# esp8266-lights-v3.net
KiCad netlist of a schematic drawn in EAGLE
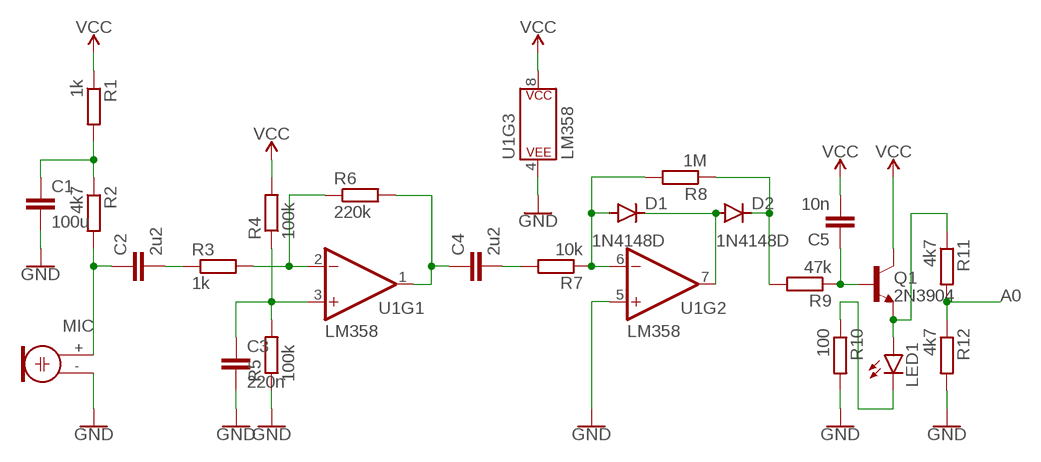
[diagram p0: schematic, sheet 1]
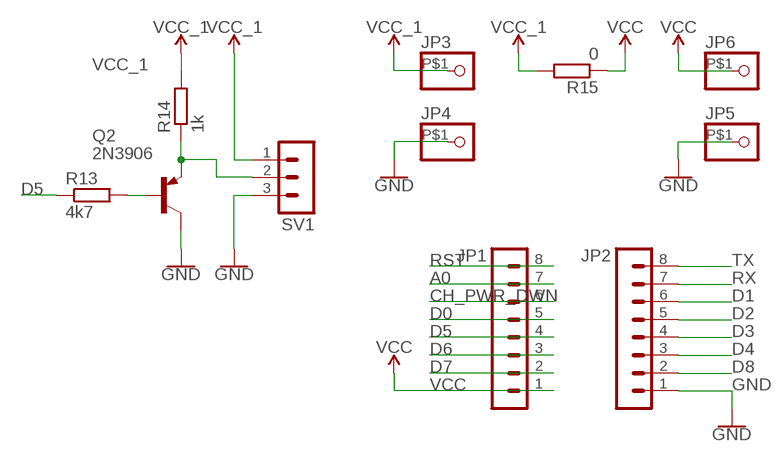
[diagram p1: schematic, sheet 2]

(export (version "E")
  (design (tool "Eeschema 10.0.6"))
  (components
    (comp (ref "JP1")
      (value "MA08-1")
      (footprint "eagle-import:MA08-1")
      (libsource (lib "eagle-import") (part "MA08-1"))
    )
    (comp (ref "JP2")
      (value "MA08-1")
      (footprint "eagle-import:MA08-1")
      (libsource (lib "eagle-import") (part "MA08-1"))
    )
    (comp (ref "JP3")
      (value "PINHD-1X1-BIGPOGO")
      (footprint "eagle-import:1X1-BIGPOGO")
      (libsource (lib "eagle-import") (part "PINHD-1X1-BIGPOGO"))
    )
    (comp (ref "JP4")
      (value "PINHD-1X1-BIGPOGO")
      (footprint "eagle-import:1X1-BIGPOGO")
      (libsource (lib "eagle-import") (part "PINHD-1X1-BIGPOGO"))
    )
    (comp (ref "JP5")
      (value "PINHD-1X1-BIGPOGO")
      (footprint "eagle-import:1X1-BIGPOGO")
      (libsource (lib "eagle-import") (part "PINHD-1X1-BIGPOGO"))
    )
    (comp (ref "JP6")
      (value "PINHD-1X1-BIGPOGO")
      (footprint "eagle-import:1X1-BIGPOGO")
      (libsource (lib "eagle-import") (part "PINHD-1X1-BIGPOGO"))
    )
    (comp (ref "Q2")
      (value "2N3906")
      (footprint "eagle-import:TO92")
      (libsource (lib "eagle-import") (part "2N3906"))
    )
    (comp (ref "R13")
      (value "4k7")
      (footprint "eagle-import:0309_10")
      (libsource (lib "eagle-import") (part "R-EU_0309/10"))
    )
    (comp (ref "R14")
      (value "1k")
      (footprint "eagle-import:0309_10")
      (libsource (lib "eagle-import") (part "R-EU_0309/10"))
    )
    (comp (ref "R15")
      (value "0")
      (footprint "eagle-import:0309_10")
      (libsource (lib "eagle-import") (part "R-EU_0309/10"))
    )
    (comp (ref "SV1")
      (value "MA03-1")
      (footprint "eagle-import:MA03-1")
      (libsource (lib "eagle-import") (part "MA03-1"))
    )
    (comp (ref "C1")
      (value "100u")
      (footprint "eagle-import:C050-024X044")
      (libsource (lib "eagle-import") (part "C-EU050-024X044"))
    )
    (comp (ref "C2")
      (value "2u2")
      (footprint "eagle-import:C050-024X044")
      (libsource (lib "eagle-import") (part "C-EU050-024X044"))
    )
    (comp (ref "C3")
      (value "220n")
      (footprint "eagle-import:C050-024X044")
      (libsource (lib "eagle-import") (part "C-EU050-024X044"))
    )
    (comp (ref "C4")
      (value "2u2")
      (footprint "eagle-import:C050-024X044")
      (libsource (lib "eagle-import") (part "C-EU050-024X044"))
    )
    (comp (ref "C5")
      (value "10n")
      (footprint "eagle-import:C050-024X044")
      (libsource (lib "eagle-import") (part "C-EU050-024X044"))
    )
    (comp (ref "D1")
      (value "1N4148D")
      (footprint "eagle-import:DO35-10")
      (libsource (lib "eagle-import") (part "1N4148DO35-10"))
    )
    (comp (ref "D2")
      (value "1N4148D")
      (footprint "eagle-import:DO35-10")
      (libsource (lib "eagle-import") (part "1N4148DO35-10"))
    )
    (comp (ref "LED1")
      (value "LED5MM")
      (footprint "eagle-import:LED5MM")
      (libsource (lib "eagle-import") (part "LED5MM"))
    )
    (comp (ref "MIC")
      (value "ELECTRET")
      (footprint "eagle-import:9.7ELECTRET")
      (libsource (lib "eagle-import") (part "ELECTRET"))
    )
    (comp (ref "Q1")
      (value "2N3904")
      (footprint "eagle-import:TO92")
      (libsource (lib "eagle-import") (part "2N3904"))
    )
    (comp (ref "R1")
      (value "1k")
      (footprint "eagle-import:0309_10")
      (libsource (lib "eagle-import") (part "R-EU_0309/10"))
    )
    (comp (ref "R2")
      (value "4k7")
      (footprint "eagle-import:0309_10")
      (libsource (lib "eagle-import") (part "R-EU_0309/10"))
    )
    (comp (ref "R3")
      (value "1k")
      (footprint "eagle-import:0309_10")
      (libsource (lib "eagle-import") (part "R-EU_0309/10"))
    )
    (comp (ref "R4")
      (value "100k")
      (footprint "eagle-import:0309_10")
      (libsource (lib "eagle-import") (part "R-EU_0309/10"))
    )
    (comp (ref "R5")
      (value "100k")
      (footprint "eagle-import:0309_10")
      (libsource (lib "eagle-import") (part "R-EU_0309/10"))
    )
    (comp (ref "R6")
      (value "220k")
      (footprint "eagle-import:0309_10")
      (libsource (lib "eagle-import") (part "R-EU_0309/10"))
    )
    (comp (ref "R7")
      (value "10k")
      (footprint "eagle-import:0309_10")
      (libsource (lib "eagle-import") (part "R-EU_0309/10"))
    )
    (comp (ref "R8")
      (value "1M")
      (footprint "eagle-import:0309_10")
      (libsource (lib "eagle-import") (part "R-EU_0309/10"))
    )
    (comp (ref "R9")
      (value "47k")
      (footprint "eagle-import:0309_10")
      (libsource (lib "eagle-import") (part "R-EU_0309/10"))
    )
    (comp (ref "R10")
      (value "100")
      (footprint "eagle-import:0309_10")
      (libsource (lib "eagle-import") (part "R-EU_0309/10"))
    )
    (comp (ref "R11")
      (value "4k7")
      (footprint "eagle-import:0309_10")
      (libsource (lib "eagle-import") (part "R-EU_0309/10"))
    )
    (comp (ref "R12")
      (value "4k7")
      (footprint "eagle-import:0309_10")
      (libsource (lib "eagle-import") (part "R-EU_0309/10"))
    )
    (comp (ref "U1")
      (value "LM358")
      (footprint "eagle-import:DIP08-KIT")
      (libsource (lib "eagle-import") (part "LM358KIT"))
    )
  )
  (nets
    (net (code "1") (name "A0") (class "Default")
      (node (ref "JP1") (pin "7") (pinfunction "7_7") (pintype "passive"))
      (node (ref "R11") (pin "2") (pinfunction "2_2") (pintype "passive"))
      (node (ref "R12") (pin "1") (pinfunction "1_1") (pintype "passive"))
    )
    (net (code "2") (name "CH_PWR_DWN") (class "Default")
      (node (ref "JP1") (pin "6") (pinfunction "6_6") (pintype "passive"))
    )
    (net (code "3") (name "D0") (class "Default")
      (node (ref "JP1") (pin "5") (pinfunction "5_5") (pintype "passive"))
    )
    (net (code "4") (name "D1") (class "Default")
      (node (ref "JP2") (pin "6") (pinfunction "6_6") (pintype "passive"))
    )
    (net (code "5") (name "D2") (class "Default")
      (node (ref "JP2") (pin "5") (pinfunction "5_5") (pintype "passive"))
    )
    (net (code "6") (name "D3") (class "Default")
      (node (ref "JP2") (pin "4") (pinfunction "4_4") (pintype "passive"))
    )
    (net (code "7") (name "D4") (class "Default")
      (node (ref "JP2") (pin "3") (pinfunction "3_3") (pintype "passive"))
    )
    (net (code "8") (name "D5") (class "Default")
      (node (ref "JP1") (pin "4") (pinfunction "4_4") (pintype "passive"))
      (node (ref "R13") (pin "1") (pinfunction "1_1") (pintype "passive"))
    )
    (net (code "9") (name "D6") (class "Default")
      (node (ref "JP1") (pin "3") (pinfunction "3_3") (pintype "passive"))
    )
    (net (code "10") (name "D7") (class "Default")
      (node (ref "JP1") (pin "2") (pinfunction "2_2") (pintype "passive"))
    )
    (net (code "11") (name "D8") (class "Default")
      (node (ref "JP2") (pin "2") (pinfunction "2_2") (pintype "passive"))
    )
    (net (code "12") (name "GND") (class "Default")
      (node (ref "C1") (pin "2") (pinfunction "2_2") (pintype "passive"))
      (node (ref "C3") (pin "2") (pinfunction "2_2") (pintype "passive"))
      (node (ref "JP2") (pin "1") (pinfunction "1_1") (pintype "passive"))
      (node (ref "JP4") (pin "P$1") (pinfunction "1_P$1") (pintype "passive"))
      (node (ref "JP5") (pin "P$1") (pinfunction "1_P$1") (pintype "passive"))
      (node (ref "MIC") (pin "-") (pinfunction "1_-") (pintype "passive"))
      (node (ref "Q2") (pin "1") (pinfunction "C_1") (pintype "passive"))
      (node (ref "R10") (pin "2") (pinfunction "2_2") (pintype "passive"))
      (node (ref "R12") (pin "2") (pinfunction "2_2") (pintype "passive"))
      (node (ref "R5") (pin "1") (pinfunction "1_1") (pintype "passive"))
      (node (ref "SV1") (pin "3") (pinfunction "3_3") (pintype "passive"))
      (node (ref "U1") (pin "4") (pinfunction "P$V-_4") (pintype "bidirectional"))
      (node (ref "U1") (pin "5") (pinfunction "+IN_5") (pintype "input"))
    )
    (net (code "13") (name "Net-(C1-Pad1)") (class "Default")
      (node (ref "C1") (pin "1") (pinfunction "1_1") (pintype "passive"))
      (node (ref "R1") (pin "2") (pinfunction "2_2") (pintype "passive"))
      (node (ref "R2") (pin "1") (pinfunction "1_1") (pintype "passive"))
    )
    (net (code "14") (name "Net-(C2-Pad2)") (class "Default")
      (node (ref "C2") (pin "2") (pinfunction "2_2") (pintype "passive"))
      (node (ref "R3") (pin "1") (pinfunction "1_1") (pintype "passive"))
    )
    (net (code "15") (name "Net-(C4-Pad2)") (class "Default")
      (node (ref "C4") (pin "2") (pinfunction "2_2") (pintype "passive"))
      (node (ref "R7") (pin "2") (pinfunction "2_2") (pintype "passive"))
    )
    (net (code "16") (name "Net-(D2-PadC)") (class "Default")
      (node (ref "D2") (pin "C") (pinfunction "C_C") (pintype "passive"))
      (node (ref "R8") (pin "1") (pinfunction "1_1") (pintype "passive"))
      (node (ref "R9") (pin "2") (pinfunction "2_2") (pintype "passive"))
    )
    (net (code "17") (name "Net-(LED1-C)") (class "Default")
      (node (ref "LED1") (pin "K") (pinfunction "C_K") (pintype "passive"))
      (node (ref "R10") (pin "1") (pinfunction "1_1") (pintype "passive"))
    )
    (net (code "18") (name "Net-(MIC-2)") (class "Default")
      (node (ref "C2") (pin "1") (pinfunction "1_1") (pintype "passive"))
      (node (ref "MIC") (pin "+") (pinfunction "2_+") (pintype "passive"))
      (node (ref "R2") (pin "2") (pinfunction "2_2") (pintype "passive"))
    )
    (net (code "19") (name "Net-(Q1-B)") (class "Default")
      (node (ref "C5") (pin "1") (pinfunction "1_1") (pintype "passive"))
      (node (ref "Q1") (pin "2") (pinfunction "B_2") (pintype "passive"))
      (node (ref "R9") (pin "1") (pinfunction "1_1") (pintype "passive"))
    )
    (net (code "20") (name "Net-(Q1-E)") (class "Default")
      (node (ref "LED1") (pin "A") (pinfunction "A_A") (pintype "passive"))
      (node (ref "Q1") (pin "3") (pinfunction "E_3") (pintype "passive"))
      (node (ref "R11") (pin "1") (pinfunction "1_1") (pintype "passive"))
    )
    (net (code "21") (name "Net-(Q2-B)") (class "Default")
      (node (ref "Q2") (pin "2") (pinfunction "B_2") (pintype "passive"))
      (node (ref "R13") (pin "2") (pinfunction "2_2") (pintype "passive"))
    )
    (net (code "22") (name "Net-(Q2-E)") (class "Default")
      (node (ref "Q2") (pin "3") (pinfunction "E_3") (pintype "passive"))
      (node (ref "R14") (pin "1") (pinfunction "1_1") (pintype "passive"))
      (node (ref "SV1") (pin "2") (pinfunction "2_2") (pintype "passive"))
    )
    (net (code "23") (name "Net-(U1A-+IN)") (class "Default")
      (node (ref "C3") (pin "1") (pinfunction "1_1") (pintype "passive"))
      (node (ref "R4") (pin "1") (pinfunction "1_1") (pintype "passive"))
      (node (ref "R5") (pin "2") (pinfunction "2_2") (pintype "passive"))
      (node (ref "U1") (pin "3") (pinfunction "+IN_3") (pintype "input"))
    )
    (net (code "24") (name "Net-(U1A--IN)") (class "Default")
      (node (ref "R3") (pin "2") (pinfunction "2_2") (pintype "passive"))
      (node (ref "R6") (pin "1") (pinfunction "1_1") (pintype "passive"))
      (node (ref "U1") (pin "2") (pinfunction "-IN_2") (pintype "input"))
    )
    (net (code "25") (name "Net-(U1A-OUT)") (class "Default")
      (node (ref "C4") (pin "1") (pinfunction "1_1") (pintype "passive"))
      (node (ref "R6") (pin "2") (pinfunction "2_2") (pintype "passive"))
      (node (ref "U1") (pin "1") (pinfunction "OUT_1") (pintype "output"))
    )
    (net (code "26") (name "Net-(U1B--IN)") (class "Default")
      (node (ref "D1") (pin "A") (pinfunction "A_A") (pintype "passive"))
      (node (ref "R7") (pin "1") (pinfunction "1_1") (pintype "passive"))
      (node (ref "R8") (pin "2") (pinfunction "2_2") (pintype "passive"))
      (node (ref "U1") (pin "6") (pinfunction "-IN_6") (pintype "input"))
    )
    (net (code "27") (name "Net-(U1B-OUT)") (class "Default")
      (node (ref "D1") (pin "C") (pinfunction "C_C") (pintype "passive"))
      (node (ref "D2") (pin "A") (pinfunction "A_A") (pintype "passive"))
      (node (ref "U1") (pin "7") (pinfunction "OUT_7") (pintype "output"))
    )
    (net (code "28") (name "RST") (class "Default")
      (node (ref "JP1") (pin "8") (pinfunction "8_8") (pintype "passive"))
    )
    (net (code "29") (name "RX") (class "Default")
      (node (ref "JP2") (pin "7") (pinfunction "7_7") (pintype "passive"))
    )
    (net (code "30") (name "TX") (class "Default")
      (node (ref "JP2") (pin "8") (pinfunction "8_8") (pintype "passive"))
    )
    (net (code "31") (name "VCC") (class "Default")
      (node (ref "C5") (pin "2") (pinfunction "2_2") (pintype "passive"))
      (node (ref "JP1") (pin "1") (pinfunction "1_1") (pintype "passive"))
      (node (ref "JP6") (pin "P$1") (pinfunction "1_P$1") (pintype "passive"))
      (node (ref "Q1") (pin "1") (pinfunction "C_1") (pintype "passive"))
      (node (ref "R1") (pin "1") (pinfunction "1_1") (pintype "passive"))
      (node (ref "R15") (pin "1") (pinfunction "1_1") (pintype "passive"))
      (node (ref "R4") (pin "2") (pinfunction "2_2") (pintype "passive"))
      (node (ref "U1") (pin "8") (pinfunction "P$V+_8") (pintype "bidirectional"))
    )
    (net (code "32") (name "VCC_1") (class "Default")
      (node (ref "JP3") (pin "P$1") (pinfunction "1_P$1") (pintype "passive"))
      (node (ref "R14") (pin "2") (pinfunction "2_2") (pintype "passive"))
      (node (ref "R15") (pin "2") (pinfunction "2_2") (pintype "passive"))
      (node (ref "SV1") (pin "1") (pinfunction "1_1") (pintype "passive"))
    )
  )
)
